# Control_Freq.net
KiCad netlist of a schematic drawn in Altium Designer
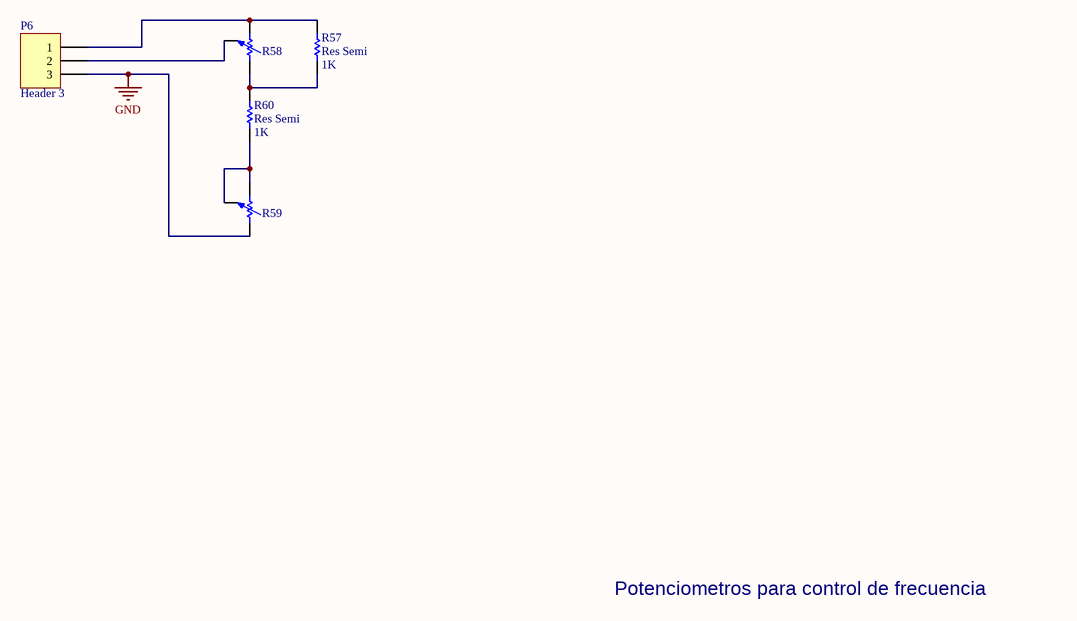
[diagram p0: Control_Freq.SchDoc]

(export (version "E")
  (design (tool "Eeschema 10.0.6"))
  (components
    (comp (ref "P6")
      (value "Header 3")
      (footprint "HDR1X3")
      (description "Header, 3-Pin")
      (fields (field (name "PUBLISHER") "Altium Limited"))
      (libsource (lib "Miscellaneous Connectors") (part "Header 3"))
    )
    (comp (ref "R57")
      (value "Res Semi")
      (footprint "2012[0805]")
      (description "Semiconductor Resistor")
      (fields (field (name "ALTIUM_VALUE") "1K") (field (name "PUBLISHER") "Altium Limited"))
      (libsource (lib "Miscellaneous Devices") (part "Res Semi"))
    )
    (comp (ref "R58") (value "Pot") (footprint "POT-eje2") (libsource (lib "epf") (part "Pot")))
    (comp (ref "R59") (value "Pot") (footprint "POT-eje2") (libsource (lib "epf") (part "Pot")))
    (comp (ref "R60")
      (value "Res Semi")
      (footprint "2012[0805]")
      (description "Semiconductor Resistor")
      (fields (field (name "ALTIUM_VALUE") "1K") (field (name "PUBLISHER") "Altium Limited"))
      (libsource (lib "Miscellaneous Devices") (part "Res Semi"))
    )
  )
  (nets
    (net (code "1") (name "GND") (class "Default")
      (node (ref "P6") (pin "3") (pinfunction "3_3") (pintype "passive"))
      (node (ref "R59") (pin "1") (pinfunction "1_1") (pintype "passive"))
    )
    (net (code "2") (name "Net-(P6-Pad1)") (class "Default")
      (node (ref "P6") (pin "1") (pinfunction "1_1") (pintype "passive"))
      (node (ref "R57") (pin "2") (pinfunction "2_2") (pintype "passive"))
      (node (ref "R58") (pin "2") (pinfunction "2_2") (pintype "passive"))
    )
    (net (code "3") (name "Net-(P6-Pad2)") (class "Default")
      (node (ref "P6") (pin "2") (pinfunction "2_2") (pintype "passive"))
      (node (ref "R58") (pin "3") (pinfunction "3_3") (pintype "passive"))
    )
    (net (code "4") (name "Net-(R57-Pad1)") (class "Default")
      (node (ref "R57") (pin "1") (pinfunction "1_1") (pintype "passive"))
      (node (ref "R58") (pin "1") (pinfunction "1_1") (pintype "passive"))
      (node (ref "R60") (pin "2") (pinfunction "2_2") (pintype "passive"))
    )
    (net (code "5") (name "Net-(R59-Pad2)") (class "Default")
      (node (ref "R59") (pin "2") (pinfunction "2_2") (pintype "passive"))
      (node (ref "R59") (pin "3") (pinfunction "3_3") (pintype "passive"))
      (node (ref "R60") (pin "1") (pinfunction "1_1") (pintype "passive"))
    )
  )
)
